# SAMD51_SoundHub_Pro_1_0_0_may2023.net
KiCad netlist of a schematic drawn in EAGLE
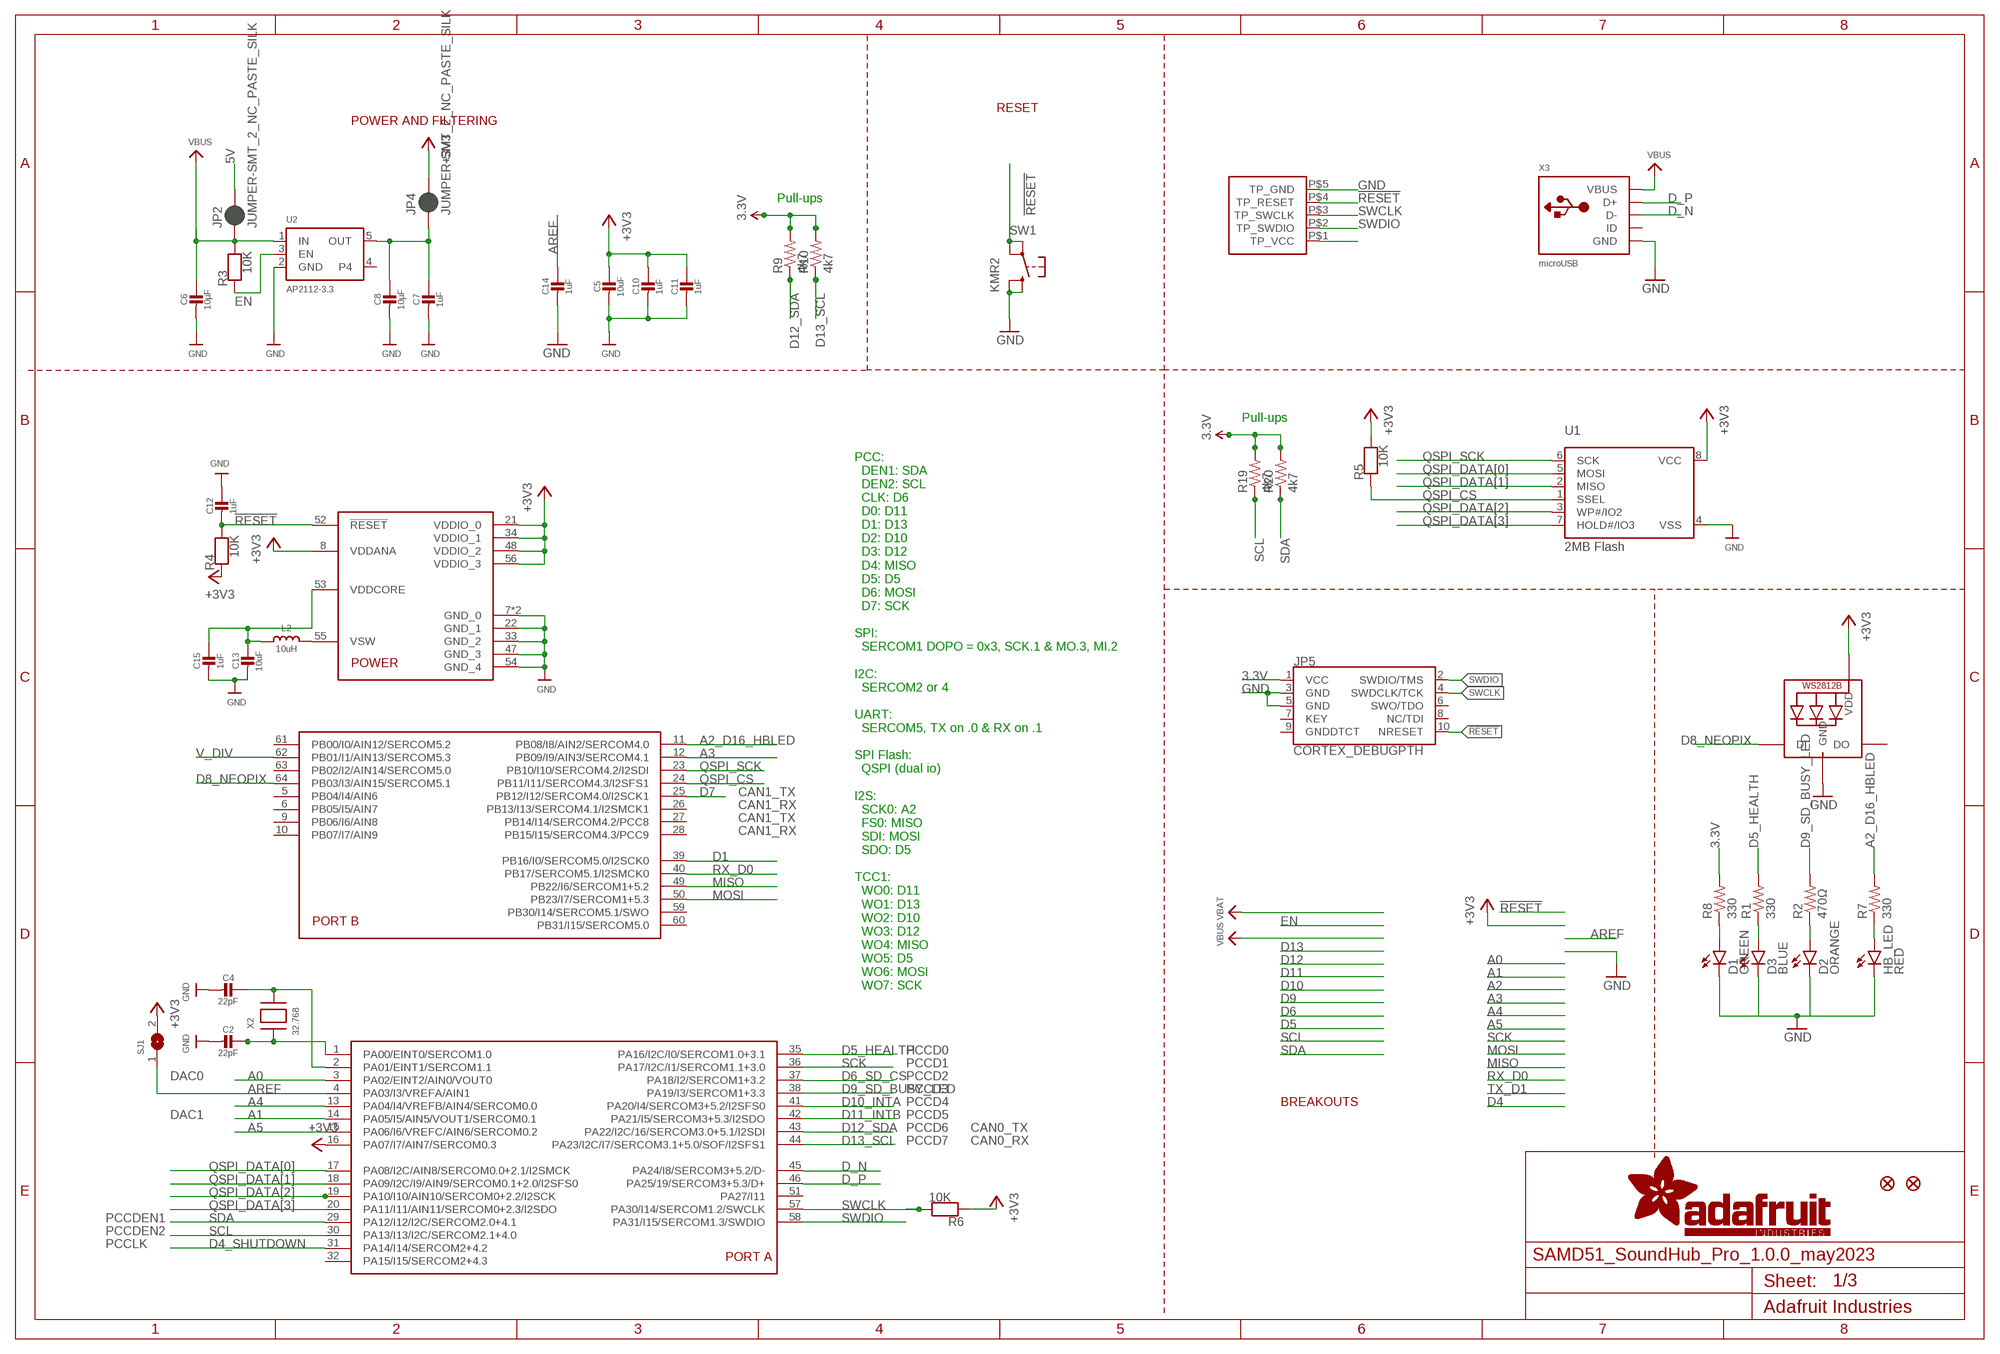
[diagram p0: schematic, sheet 1]
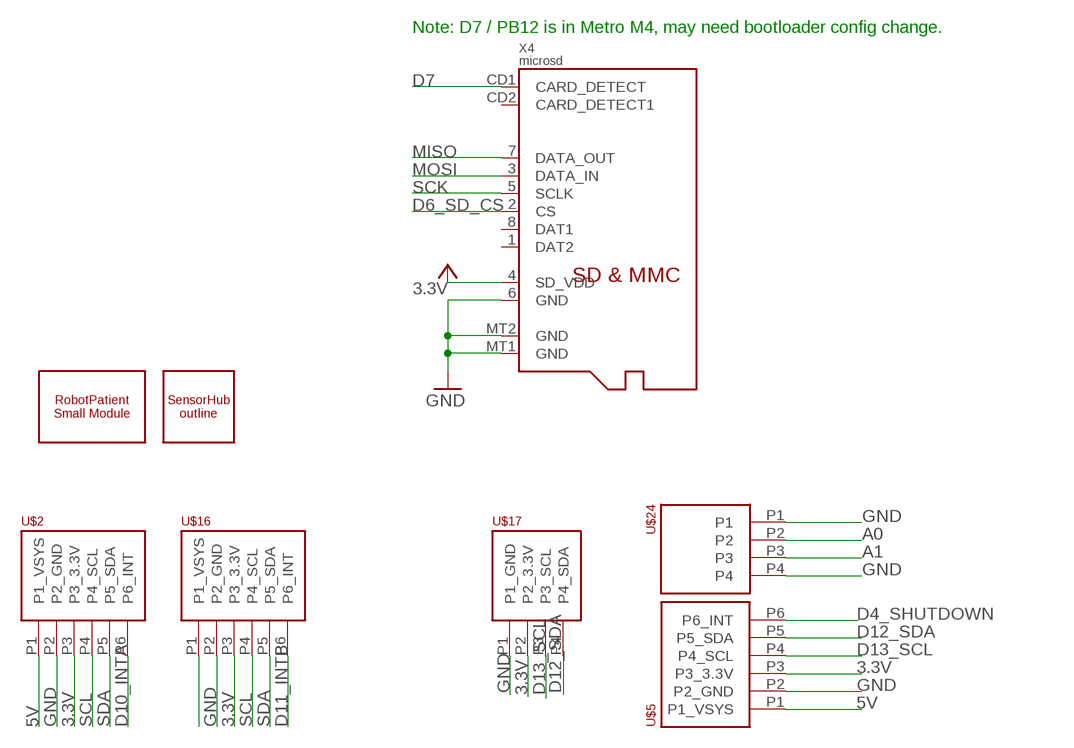
[diagram p1: schematic, sheet 2]

(export (version "E")
  (design (tool "Eeschema 10.0.6"))
  (components
    (comp (ref "C2")
      (value "22pF")
      (footprint "eagle-import:0603-NO")
      (libsource (lib "eagle-import") (part "CAP_CERAMIC0603_NO"))
    )
    (comp (ref "C4")
      (value "22pF")
      (footprint "eagle-import:0603-NO")
      (libsource (lib "eagle-import") (part "CAP_CERAMIC0603_NO"))
    )
    (comp (ref "C5")
      (value "10uF")
      (footprint "eagle-import:0805-NO")
      (libsource (lib "eagle-import") (part "CAP_CERAMIC0805-NOOUTLINE"))
    )
    (comp (ref "C6")
      (value "10µF")
      (footprint "eagle-import:0805-NO")
      (libsource (lib "eagle-import") (part "CAP_CERAMIC0805-NOOUTLINE"))
    )
    (comp (ref "C7")
      (value "1uF")
      (footprint "eagle-import:0603-NO")
      (libsource (lib "eagle-import") (part "CAP_CERAMIC0603_NO"))
    )
    (comp (ref "C8")
      (value "10µF")
      (footprint "eagle-import:0805-NO")
      (fields (field (name "REV") "E"))
      (libsource (lib "eagle-import") (part "CAP_CERAMIC0805-NOOUTLINE"))
    )
    (comp (ref "C10")
      (value "1uF")
      (footprint "eagle-import:0603-NO")
      (libsource (lib "eagle-import") (part "CAP_CERAMIC0603_NO"))
    )
    (comp (ref "C11")
      (value "1uF")
      (footprint "eagle-import:0603-NO")
      (libsource (lib "eagle-import") (part "CAP_CERAMIC0603_NO"))
    )
    (comp (ref "C12")
      (value "1uF")
      (footprint "eagle-import:0603-NO")
      (libsource (lib "eagle-import") (part "CAP_CERAMIC0603_NO"))
    )
    (comp (ref "C13")
      (value "10uF")
      (footprint "eagle-import:0805-NO")
      (libsource (lib "eagle-import") (part "CAP_CERAMIC0805-NOOUTLINE"))
    )
    (comp (ref "C14")
      (value "1uF")
      (footprint "eagle-import:0603-NO")
      (libsource (lib "eagle-import") (part "CAP_CERAMIC0603_NO"))
    )
    (comp (ref "C15")
      (value "1uF")
      (footprint "eagle-import:0603-NO")
      (libsource (lib "eagle-import") (part "CAP_CERAMIC0603_NO"))
    )
    (comp (ref "D1")
      (value "GREEN")
      (footprint "eagle-import:LED-0603@1")
      (libsource (lib "eagle-import") (part "LED-BLUE0603"))
    )
    (comp (ref "D2")
      (value "ORANGE")
      (footprint "eagle-import:LED-0603")
      (libsource (lib "eagle-import") (part "LED-RED0603"))
    )
    (comp (ref "D3")
      (value "BLUE")
      (footprint "eagle-import:LED-0603@1")
      (libsource (lib "eagle-import") (part "LED-BLUE0603"))
    )
    (comp (ref "HB_LED")
      (value "RED")
      (footprint "eagle-import:LED-0603")
      (libsource (lib "eagle-import") (part "LED-RED0603"))
    )
    (comp (ref "JP2")
      (value "JUMPER-SMT_2_NC_PASTE_SILK")
      (footprint "eagle-import:SMT-JUMPER_2_NC_PASTE_SILK")
      (libsource (lib "eagle-import") (part "JUMPER-SMT_2_NC_PASTE_SILK"))
    )
    (comp (ref "JP4")
      (value "JUMPER-SMT_2_NC_PASTE_SILK")
      (footprint "eagle-import:SMT-JUMPER_2_NC_PASTE_SILK")
      (libsource (lib "eagle-import") (part "JUMPER-SMT_2_NC_PASTE_SILK"))
    )
    (comp (ref "JP5")
      (value "CORTEX_DEBUGPTH")
      (footprint "eagle-import:2X5-PTH-1.27MM")
      (libsource (lib "eagle-import") (part "CORTEX_DEBUGPTH"))
    )
    (comp (ref "L2")
      (value "10uH")
      (footprint "eagle-import:INDUCTOR_1007")
      (libsource (lib "eagle-import") (part "INDUCTOR"))
    )
    (comp (ref "LED1")
      (value "WS2812B3535")
      (footprint "eagle-import:LED3535")
      (libsource (lib "eagle-import") (part "WS2812B3535"))
    )
    (comp (ref "R1")
      (value "330")
      (footprint "eagle-import:0603-RES")
      (libsource (lib "eagle-import") (part "330OHM1/10W1%(0603)"))
    )
    (comp (ref "R2")
      (value "470Ω")
      (footprint "eagle-import:0603-RES")
      (libsource (lib "eagle-import") (part "330OHM1/10W1%(0603)"))
    )
    (comp (ref "R3")
      (value "10K")
      (footprint "eagle-import:0603-NO")
      (libsource (lib "eagle-import") (part "RESISTOR_0603_NOOUT"))
    )
    (comp (ref "R4")
      (value "10K")
      (footprint "eagle-import:0603-NO")
      (libsource (lib "eagle-import") (part "RESISTOR_0603_NOOUT"))
    )
    (comp (ref "R5")
      (value "10K")
      (footprint "eagle-import:0603-NO")
      (libsource (lib "eagle-import") (part "RESISTOR_0603_NOOUT"))
    )
    (comp (ref "R6")
      (value "10K")
      (footprint "eagle-import:0603-NO")
      (libsource (lib "eagle-import") (part "RESISTOR_0603_NOOUT"))
    )
    (comp (ref "R7")
      (value "330")
      (footprint "eagle-import:0603-RES")
      (libsource (lib "eagle-import") (part "330OHM1/10W1%(0603)"))
    )
    (comp (ref "R8")
      (value "330")
      (footprint "eagle-import:0603-RES")
      (libsource (lib "eagle-import") (part "330OHM1/10W1%(0603)"))
    )
    (comp (ref "R9")
      (value "4k7")
      (footprint "eagle-import:0603-RES")
      (libsource (lib "eagle-import") (part "47KOHM1/10W1%(0603)"))
    )
    (comp (ref "R10")
      (value "4k7")
      (footprint "eagle-import:0603-RES")
      (libsource (lib "eagle-import") (part "47KOHM1/10W1%(0603)"))
    )
    (comp (ref "R19")
      (value "4k7")
      (footprint "eagle-import:0603-RES")
      (libsource (lib "eagle-import") (part "47KOHM1/10W1%(0603)"))
    )
    (comp (ref "R20")
      (value "4k7")
      (footprint "eagle-import:0603-RES")
      (libsource (lib "eagle-import") (part "47KOHM1/10W1%(0603)"))
    )
    (comp (ref "SJ1")
      (value "SOLDERJUMPERCLOSED")
      (footprint "eagle-import:SOLDERJUMPER_CLOSEDWIRE")
      (libsource (lib "eagle-import") (part "SOLDERJUMPERCLOSED"))
    )
    (comp (ref "SW1")
      (value "KMR2")
      (footprint "eagle-import:BTN_KMR2_4.6X2.8")
      (libsource (lib "eagle-import") (part "SWITCH_TACT_SMT4.6X2.8"))
    )
    (comp (ref "U$12")
      (value "HUB_TESTPINSHUBS")
      (footprint "eagle-import:TEST_PINS")
      (libsource (lib "eagle-import") (part "HUB_TESTPINSHUBS"))
    )
    (comp (ref "U$14")
      (value "ATSAMD51J")
      (footprint "eagle-import:PQFN64-1")
      (libsource (lib "eagle-import") (part "ATSAMD51J"))
    )
    (comp (ref "U$34")
      (value "FIDUCIAL_1MM")
      (footprint "eagle-import:FIDUCIAL_1MM")
      (libsource (lib "eagle-import") (part "FIDUCIAL_1MM"))
    )
    (comp (ref "U$35")
      (value "FIDUCIAL_1MM")
      (footprint "eagle-import:FIDUCIAL_1MM")
      (libsource (lib "eagle-import") (part "FIDUCIAL_1MM"))
    )
    (comp (ref "U1")
      (value "2MB Flash")
      (footprint "eagle-import:USON8")
      (libsource (lib "eagle-import") (part "SPIFLASH_8PINUX"))
    )
    (comp (ref "U2")
      (value "AP2112-3.3")
      (footprint "eagle-import:SOT23-5")
      (libsource (lib "eagle-import") (part "VREG_SOT23-5"))
    )
    (comp (ref "X2")
      (value "32.768")
      (footprint "eagle-import:XTAL3215")
      (libsource (lib "eagle-import") (part "XTAL-3.2X1.5"))
    )
    (comp (ref "X3")
      (value "microUSB")
      (footprint "eagle-import:4UCONN_20329_V2")
      (libsource (lib "eagle-import") (part "USB_MICRO_20329_V2"))
    )
    (comp (ref "U$2")
      (value "PHOENIX_PTSM_M6_TH_I2CPPANGLE")
      (footprint "eagle-import:PTSM_M6_THRHOLE")
      (libsource (lib "eagle-import") (part "PHOENIX_PTSM_M6_TH_I2CPPANGLE"))
    )
    (comp (ref "U$5")
      (value "PHOENIX_PTSM_M6_TH_I2CPPANGLE")
      (footprint "eagle-import:PTSM_M6_THRHOLE")
      (libsource (lib "eagle-import") (part "PHOENIX_PTSM_M6_TH_I2CPPANGLE"))
    )
    (comp (ref "U$7")
      (value "SENSORHUB_PROFILEUSB_LEFT")
      (footprint "eagle-import:SENSORHUB_OUTLINE_USB_NOTCH_LEFT")
      (libsource (lib "eagle-import") (part "SENSORHUB_PROFILEUSB_LEFT"))
    )
    (comp (ref "U$9")
      (value "ROBOTPATIENT_SMALL_MODULEOUTLINE")
      (footprint "eagle-import:ROBOTPATIENT_SMALL")
      (libsource (lib "eagle-import") (part "ROBOTPATIENT_SMALL_MODULEOUTLINE"))
    )
    (comp (ref "U$16")
      (value "PHOENIX_PTSM_M6_TH_I2CPPANGLE")
      (footprint "eagle-import:PTSM_M6_THRHOLE")
      (libsource (lib "eagle-import") (part "PHOENIX_PTSM_M6_TH_I2CPPANGLE"))
    )
    (comp (ref "U$17")
      (value "PHOENIX_PTSM_M4_THANGLE")
      (footprint "eagle-import:PTSM_M4_TH")
      (libsource (lib "eagle-import") (part "PHOENIX_PTSM_M4_THANGLE"))
    )
    (comp (ref "U$24")
      (value "PHOENIX_PTSM_M4_TH_ANGLE")
      (footprint "eagle-import:PTSM_M4_TH_ANGLE_NEUTRAL")
      (libsource (lib "eagle-import") (part "PHOENIX_PTSM_M4_TH_ANGLE"))
    )
    (comp (ref "X4")
      (value "microsd")
      (footprint "eagle-import:MICROSD")
      (libsource (lib "eagle-import") (part "MICROSD"))
    )
  )
  (nets
    (net (code "1") (name "3.3V") (class "Default")
      (node (ref "C10") (pin "1") (pinfunction "1_1") (pintype "passive"))
      (node (ref "C11") (pin "1") (pinfunction "1_1") (pintype "passive"))
      (node (ref "C5") (pin "1") (pinfunction "1_1") (pintype "passive"))
      (node (ref "JP4") (pin "2") (pinfunction "2_2") (pintype "passive"))
      (node (ref "JP5") (pin "1") (pinfunction "VCC_1") (pintype "bidirectional"))
      (node (ref "LED1") (pin "2") (pinfunction "VDD_2") (pintype "power_in"))
      (node (ref "R10") (pin "2") (pinfunction "2_2") (pintype "passive"))
      (node (ref "R19") (pin "2") (pinfunction "2_2") (pintype "passive"))
      (node (ref "R20") (pin "2") (pinfunction "2_2") (pintype "passive"))
      (node (ref "R4") (pin "1") (pinfunction "1_1") (pintype "passive"))
      (node (ref "R5") (pin "2") (pinfunction "2_2") (pintype "passive"))
      (node (ref "R6") (pin "1") (pinfunction "1_1") (pintype "passive"))
      (node (ref "R8") (pin "2") (pinfunction "2_2") (pintype "passive"))
      (node (ref "R9") (pin "2") (pinfunction "2_2") (pintype "passive"))
      (node (ref "SJ1") (pin "2") (pinfunction "2_2") (pintype "passive"))
      (node (ref "U$12") (pin "P$1") (pinfunction "TP_VCC_P$1") (pintype "bidirectional"))
      (node (ref "U$14") (pin "16") (pinfunction "PA07/I7/AIN7/SERCOM0.3_16") (pintype "bidirectional"))
      (node (ref "U$14") (pin "21") (pinfunction "VDDIO_0_21") (pintype "bidirectional"))
      (node (ref "U$14") (pin "34") (pinfunction "VDDIO_1_34") (pintype "bidirectional"))
      (node (ref "U$14") (pin "48") (pinfunction "VDDIO_2_48") (pintype "bidirectional"))
      (node (ref "U$14") (pin "56") (pinfunction "VDDIO_3_56") (pintype "bidirectional"))
      (node (ref "U$14") (pin "8") (pinfunction "VDDANA_8") (pintype "bidirectional"))
      (node (ref "U$16") (pin "P3") (pinfunction "P3_3.3V_P3") (pintype "power_in"))
      (node (ref "U$17") (pin "P2") (pinfunction "P2_3.3V_P2") (pintype "power_in"))
      (node (ref "U$2") (pin "P3") (pinfunction "P3_3.3V_P3") (pintype "power_in"))
      (node (ref "U$5") (pin "P3") (pinfunction "P3_3.3V_P3") (pintype "power_in"))
      (node (ref "U1") (pin "8") (pinfunction "VCC_8") (pintype "bidirectional"))
      (node (ref "X4") (pin "4") (pinfunction "SD_VDD_4") (pintype "power_in"))
    )
    (net (code "2") (name "5V") (class "Default")
      (node (ref "JP2") (pin "2") (pinfunction "2_2") (pintype "passive"))
      (node (ref "U$16") (pin "P1") (pinfunction "P1_VSYS_P1") (pintype "power_in"))
      (node (ref "U$2") (pin "P1") (pinfunction "P1_VSYS_P1") (pintype "power_in"))
      (node (ref "U$5") (pin "P1") (pinfunction "P1_VSYS_P1") (pintype "power_in"))
    )
    (net (code "3") (name "A0") (class "Default")
      (node (ref "U$14") (pin "3") (pinfunction "PA02/EINT2/AIN0/VOUT0_3") (pintype "bidirectional"))
      (node (ref "U$24") (pin "P2") (pinfunction "P2_P2") (pintype "power_in"))
    )
    (net (code "4") (name "A1") (class "Default")
      (node (ref "U$14") (pin "14") (pinfunction "PA05/I5/AIN5/VOUT1/SERCOM0.1_14") (pintype "bidirectional"))
      (node (ref "U$24") (pin "P3") (pinfunction "P3_P3") (pintype "power_in"))
    )
    (net (code "6") (name "A2_D16_HBLED") (class "Default")
      (node (ref "R7") (pin "2") (pinfunction "2_2") (pintype "passive"))
      (node (ref "U$14") (pin "11") (pinfunction "PB08/I8/AIN2/SERCOM4.0_11") (pintype "bidirectional"))
    )
    (net (code "7") (name "A3") (class "Default")
      (node (ref "U$14") (pin "12") (pinfunction "PB09/I9/AIN3/SERCOM4.1_12") (pintype "bidirectional"))
    )
    (net (code "8") (name "A4") (class "Default")
      (node (ref "U$14") (pin "13") (pinfunction "PA04/I4/VREFB/AIN4/SERCOM0.0_13") (pintype "bidirectional"))
    )
    (net (code "9") (name "A5") (class "Default")
      (node (ref "U$14") (pin "15") (pinfunction "PA06/I6/VREFC/AIN6/SERCOM0.2_15") (pintype "bidirectional"))
    )
    (net (code "10") (name "AREF") (class "Default")
      (node (ref "C14") (pin "1") (pinfunction "1_1") (pintype "passive"))
      (node (ref "SJ1") (pin "1") (pinfunction "1_1") (pintype "passive"))
      (node (ref "U$14") (pin "4") (pinfunction "PA03/I3/VREFA/AIN1_4") (pintype "bidirectional"))
    )
    (net (code "11") (name "D1") (class "Default")
      (node (ref "U$14") (pin "39") (pinfunction "PB16/I0/SERCOM5.0/I2SCK0_39") (pintype "bidirectional"))
    )
    (net (code "13") (name "D4_SHUTDOWN") (class "Default")
      (node (ref "U$14") (pin "31") (pinfunction "PA14/I14/SERCOM2+4.2_31") (pintype "bidirectional"))
      (node (ref "U$5") (pin "P6") (pinfunction "P6_INT_P6") (pintype "power_in"))
    )
    (net (code "15") (name "D5_HEALTH") (class "Default")
      (node (ref "R1") (pin "2") (pinfunction "2_2") (pintype "passive"))
      (node (ref "U$14") (pin "35") (pinfunction "PA16/I2C/I0/SERCOM1.0+3.1_35") (pintype "bidirectional"))
    )
    (net (code "17") (name "D6_SD_CS") (class "Default")
      (node (ref "U$14") (pin "37") (pinfunction "PA18/I2/SERCOM1+3.2_37") (pintype "bidirectional"))
      (node (ref "X4") (pin "2") (pinfunction "CS_2") (pintype "input"))
    )
    (net (code "18") (name "D7") (class "Default")
      (node (ref "U$14") (pin "25") (pinfunction "PB12/I12/SERCOM4.0/I2SCK1_25") (pintype "bidirectional"))
      (node (ref "X4") (pin "CD1") (pinfunction "CARD_DETECT_CD1") (pintype "passive"))
    )
    (net (code "19") (name "D8_NEOPIX") (class "Default")
      (node (ref "LED1") (pin "1") (pinfunction "DI_1") (pintype "input"))
      (node (ref "U$14") (pin "64") (pinfunction "PB03/I3/AIN15/SERCOM5.1_64") (pintype "bidirectional"))
    )
    (net (code "21") (name "D9_SD_BUSY_LED") (class "Default")
      (node (ref "R2") (pin "2") (pinfunction "2_2") (pintype "passive"))
      (node (ref "U$14") (pin "38") (pinfunction "PA19/I3/SERCOM1+3.3_38") (pintype "bidirectional"))
    )
    (net (code "23") (name "D10_INTA") (class "Default")
      (node (ref "U$14") (pin "41") (pinfunction "PA20/I4/SERCOM3+5.2/I2SFS0_41") (pintype "bidirectional"))
      (node (ref "U$2") (pin "P6") (pinfunction "P6_INT_P6") (pintype "power_in"))
    )
    (net (code "25") (name "D11_INTB") (class "Default")
      (node (ref "U$14") (pin "42") (pinfunction "PA21/I5/SERCOM3+5.3/I2SDO_42") (pintype "bidirectional"))
      (node (ref "U$16") (pin "P6") (pinfunction "P6_INT_P6") (pintype "power_in"))
    )
    (net (code "27") (name "D12_SDA") (class "Default")
      (node (ref "R9") (pin "1") (pinfunction "1_1") (pintype "passive"))
      (node (ref "U$14") (pin "43") (pinfunction "PA22/I2C/16/SERCOM3.0+5.1/I2SDI_43") (pintype "bidirectional"))
      (node (ref "U$17") (pin "P4") (pinfunction "P4_SDA_P4") (pintype "bidirectional"))
      (node (ref "U$5") (pin "P5") (pinfunction "P5_SDA_P5") (pintype "bidirectional"))
    )
    (net (code "29") (name "D13_SCL") (class "Default")
      (node (ref "R10") (pin "1") (pinfunction "1_1") (pintype "passive"))
      (node (ref "U$14") (pin "44") (pinfunction "PA23/I2C/I7/SERCOM3.1+5.0/SOF/I2SFS1_44") (pintype "bidirectional"))
      (node (ref "U$17") (pin "P3") (pinfunction "P3_SCL_P3") (pintype "bidirectional"))
      (node (ref "U$5") (pin "P4") (pinfunction "P4_SCL_P4") (pintype "bidirectional"))
    )
    (net (code "30") (name "D_N") (class "Default")
      (node (ref "U$14") (pin "45") (pinfunction "PA24/I8/SERCOM3+5.2/D-_45") (pintype "bidirectional"))
      (node (ref "X3") (pin "D-") (pinfunction "D-_D-") (pintype "bidirectional"))
    )
    (net (code "31") (name "D_P") (class "Default")
      (node (ref "U$14") (pin "46") (pinfunction "PA25/19/SERCOM3+5.3/D+_46") (pintype "bidirectional"))
      (node (ref "X3") (pin "D+") (pinfunction "D+_D+") (pintype "bidirectional"))
    )
    (net (code "32") (name "EN") (class "Default")
      (node (ref "R3") (pin "1") (pinfunction "1_1") (pintype "passive"))
      (node (ref "U2") (pin "3") (pinfunction "EN_3") (pintype "input"))
    )
    (net (code "33") (name "GND") (class "Default")
      (node (ref "C10") (pin "2") (pinfunction "2_2") (pintype "passive"))
      (node (ref "C11") (pin "2") (pinfunction "2_2") (pintype "passive"))
      (node (ref "C12") (pin "1") (pinfunction "1_1") (pintype "passive"))
      (node (ref "C13") (pin "2") (pinfunction "2_2") (pintype "passive"))
      (node (ref "C14") (pin "2") (pinfunction "2_2") (pintype "passive"))
      (node (ref "C15") (pin "2") (pinfunction "2_2") (pintype "passive"))
      (node (ref "C2") (pin "2") (pinfunction "2_2") (pintype "passive"))
      (node (ref "C4") (pin "2") (pinfunction "2_2") (pintype "passive"))
      (node (ref "C5") (pin "2") (pinfunction "2_2") (pintype "passive"))
      (node (ref "C6") (pin "2") (pinfunction "2_2") (pintype "passive"))
      (node (ref "C7") (pin "2") (pinfunction "2_2") (pintype "passive"))
      (node (ref "C8") (pin "2") (pinfunction "2_2") (pintype "passive"))
      (node (ref "D1") (pin "C") (pinfunction "C_C") (pintype "passive"))
      (node (ref "HB_LED") (pin "C") (pinfunction "C_C") (pintype "passive"))
      (node (ref "JP5") (pin "3") (pinfunction "GND_3") (pintype "bidirectional"))
      (node (ref "JP5") (pin "5") (pinfunction "GND_5") (pintype "bidirectional"))
      (node (ref "LED1") (pin "4") (pinfunction "GND_4") (pintype "power_in"))
      (node (ref "SW1") (pin "B") (pinfunction "S_B") (pintype "passive"))
      (node (ref "SW1") (pin "B'") (pinfunction "S1_B'") (pintype "passive"))
      (node (ref "U$12") (pin "P$5") (pinfunction "TP_GND_P$5") (pintype "bidirectional"))
      (node (ref "U$14") (pin "22") (pinfunction "GND_1_22") (pintype "bidirectional"))
      (node (ref "U$14") (pin "33") (pinfunction "GND_2_33") (pintype "bidirectional"))
      (node (ref "U$14") (pin "47") (pinfunction "GND_3_47") (pintype "bidirectional"))
      (node (ref "U$14") (pin "54") (pinfunction "GND_4_54") (pintype "bidirectional"))
      (node (ref "U$14") (pin "7") (pinfunction "GND_0_7") (pintype "bidirectional"))
      (node (ref "U$14") (pin "EXP") (pinfunction "GND_0_EXP") (pintype "bidirectional"))
      (node (ref "U$16") (pin "P2") (pinfunction "P2_GND_P2") (pintype "power_in"))
      (node (ref "U$17") (pin "P1") (pinfunction "P1_GND_P1") (pintype "power_in"))
      (node (ref "U$2") (pin "P2") (pinfunction "P2_GND_P2") (pintype "power_in"))
      (node (ref "U$24") (pin "P1") (pinfunction "P1_P1") (pintype "power_in"))
      (node (ref "U$24") (pin "P4") (pinfunction "P4_P4") (pintype "power_in"))
      (node (ref "U$5") (pin "P2") (pinfunction "P2_GND_P2") (pintype "power_in"))
      (node (ref "U1") (pin "4") (pinfunction "VSS_4") (pintype "bidirectional"))
      (node (ref "U2") (pin "2") (pinfunction "GND_2") (pintype "power_in"))
      (node (ref "X3") (pin "BASE@1") (pinfunction "GND_BASE@1") (pintype "power_in"))
      (node (ref "X3") (pin "BASE@2") (pinfunction "GND_BASE@2") (pintype "power_in"))
      (node (ref "X3") (pin "GND") (pinfunction "GND_GND") (pintype "power_in"))
      (node (ref "X3") (pin "SPRT@1") (pinfunction "GND_SPRT@1") (pintype "power_in"))
      (node (ref "X3") (pin "SPRT@2") (pinfunction "GND_SPRT@2") (pintype "power_in"))
      (node (ref "X3") (pin "SPRT@3") (pinfunction "GND_SPRT@3") (pintype "power_in"))
      (node (ref "X3") (pin "SPRT@4") (pinfunction "GND_SPRT@4") (pintype "power_in"))
      (node (ref "X4") (pin "6") (pinfunction "GND_6") (pintype "power_in"))
      (node (ref "X4") (pin "MT1") (pinfunction "GND_MT1") (pintype "power_in"))
      (node (ref "X4") (pin "MT2") (pinfunction "GND_MT2") (pintype "power_in"))
    )
    (net (code "34") (name "MISO") (class "Default")
      (node (ref "U$14") (pin "49") (pinfunction "PB22/I6/SERCOM1+5.2_49") (pintype "bidirectional"))
      (node (ref "X4") (pin "7") (pinfunction "DATA_OUT_7") (pintype "output"))
    )
    (net (code "35") (name "MOSI") (class "Default")
      (node (ref "U$14") (pin "50") (pinfunction "PB23/I7/SERCOM1+5.3_50") (pintype "bidirectional"))
      (node (ref "X4") (pin "3") (pinfunction "DATA_IN_3") (pintype "input"))
    )
    (net (code "36") (name "Net-(D1-PadA)") (class "Default")
      (node (ref "D1") (pin "A") (pinfunction "A_A") (pintype "passive"))
      (node (ref "R8") (pin "1") (pinfunction "1_1") (pintype "passive"))
    )
    (net (code "37") (name "Net-(D2-PadA)") (class "Default")
      (node (ref "D2") (pin "A") (pinfunction "A_A") (pintype "passive"))
      (node (ref "R2") (pin "1") (pinfunction "1_1") (pintype "passive"))
    )
    (net (code "38") (name "Net-(D3-PadA)") (class "Default")
      (node (ref "D3") (pin "A") (pinfunction "A_A") (pintype "passive"))
      (node (ref "R1") (pin "1") (pinfunction "1_1") (pintype "passive"))
    )
    (net (code "39") (name "Net-(HB_LED-PadA)") (class "Default")
      (node (ref "HB_LED") (pin "A") (pinfunction "A_A") (pintype "passive"))
      (node (ref "R7") (pin "1") (pinfunction "1_1") (pintype "passive"))
    )
    (net (code "40") (name "Net-(L2-1)") (class "Default")
      (node (ref "C13") (pin "1") (pinfunction "1_1") (pintype "passive"))
      (node (ref "C15") (pin "1") (pinfunction "1_1") (pintype "passive"))
      (node (ref "L2") (pin "P$1") (pinfunction "1_P$1") (pintype "passive"))
      (node (ref "U$14") (pin "53") (pinfunction "VDDCORE_53") (pintype "bidirectional"))
    )
    (net (code "41") (name "Net-(L2-2)") (class "Default")
      (node (ref "L2") (pin "P$2") (pinfunction "2_P$2") (pintype "passive"))
      (node (ref "U$14") (pin "55") (pinfunction "VSW_55") (pintype "bidirectional"))
    )
    (net (code "42") (name "Net-(U$14A-PA00{slash}EINT0{slash}SERCOM1.0)") (class "Default")
      (node (ref "C2") (pin "1") (pinfunction "1_1") (pintype "passive"))
      (node (ref "U$14") (pin "1") (pinfunction "PA00/EINT0/SERCOM1.0_1") (pintype "bidirectional"))
      (node (ref "X2") (pin "P$1") (pinfunction "P$1_P$1") (pintype "bidirectional"))
    )
    (net (code "43") (name "Net-(U$14A-PA01{slash}EINT1{slash}SERCOM1.1)") (class "Default")
      (node (ref "C4") (pin "1") (pinfunction "1_1") (pintype "passive"))
      (node (ref "U$14") (pin "2") (pinfunction "PA01/EINT1/SERCOM1.1_2") (pintype "bidirectional"))
      (node (ref "X2") (pin "P$2") (pinfunction "P$2_P$2") (pintype "bidirectional"))
    )
    (net (code "44") (name "Net-(U2-OUT)") (class "Default")
      (node (ref "C7") (pin "1") (pinfunction "1_1") (pintype "passive"))
      (node (ref "C8") (pin "1") (pinfunction "1_1") (pintype "passive"))
      (node (ref "JP4") (pin "1") (pinfunction "1_1") (pintype "passive"))
      (node (ref "U2") (pin "5") (pinfunction "OUT_5") (pintype "power_in"))
    )
    (net (code "45") (name "QSPI_CS") (class "Default")
      (node (ref "R5") (pin "1") (pinfunction "1_1") (pintype "passive"))
      (node (ref "U$14") (pin "24") (pinfunction "PB11/I11/SERCOM4.3/I2SFS1_24") (pintype "bidirectional"))
      (node (ref "U1") (pin "1") (pinfunction "SSEL_1") (pintype "bidirectional"))
    )
    (net (code "46") (name "QSPI_DATA[0]") (class "Default")
      (node (ref "U$14") (pin "17") (pinfunction "PA08/I2C/AIN8/SERCOM0.0+2.1/I2SMCK_17") (pintype "bidirectional"))
      (node (ref "U1") (pin "5") (pinfunction "MOSI_5") (pintype "bidirectional"))
    )
    (net (code "47") (name "QSPI_DATA[1]") (class "Default")
      (node (ref "U$14") (pin "18") (pinfunction "PA09/I2C/I9/AIN9/SERCOM0.1+2.0/I2SFS0_18") (pintype "bidirectional"))
      (node (ref "U1") (pin "2") (pinfunction "MISO_2") (pintype "bidirectional"))
    )
    (net (code "48") (name "QSPI_DATA[2]") (class "Default")
      (node (ref "U$14") (pin "19") (pinfunction "PA10/I10/AIN10/SERCOM0+2.2/I2SCK_19") (pintype "bidirectional"))
      (node (ref "U1") (pin "3") (pinfunction "WP#/IO2_3") (pintype "bidirectional"))
    )
    (net (code "49") (name "QSPI_DATA[3]") (class "Default")
      (node (ref "U$14") (pin "20") (pinfunction "PA11/I11/AIN11/SERCOM0+2.3/I2SDO_20") (pintype "bidirectional"))
      (node (ref "U1") (pin "7") (pinfunction "HOLD#/IO3_7") (pintype "bidirectional"))
    )
    (net (code "50") (name "QSPI_SCK") (class "Default")
      (node (ref "U$14") (pin "23") (pinfunction "PB10/I10/SERCOM4.2/I2SDI_23") (pintype "bidirectional"))
      (node (ref "U1") (pin "6") (pinfunction "SCK_6") (pintype "bidirectional"))
    )
    (net (code "51") (name "RX_D0") (class "Default")
      (node (ref "U$14") (pin "40") (pinfunction "PB17/SERCOM5.1/I2SMCK0_40") (pintype "bidirectional"))
    )
    (net (code "52") (name "SCK") (class "Default")
      (node (ref "U$14") (pin "36") (pinfunction "PA17/I2C/I1/SERCOM1.1+3.0_36") (pintype "bidirectional"))
      (node (ref "X4") (pin "5") (pinfunction "SCLK_5") (pintype "input"))
    )
    (net (code "53") (name "SCL") (class "Default")
      (node (ref "R19") (pin "1") (pinfunction "1_1") (pintype "passive"))
      (node (ref "U$14") (pin "30") (pinfunction "PA13/I13/I2C/SERCOM2.1+4.0_30") (pintype "bidirectional"))
      (node (ref "U$16") (pin "P4") (pinfunction "P4_SCL_P4") (pintype "bidirectional"))
      (node (ref "U$2") (pin "P4") (pinfunction "P4_SCL_P4") (pintype "bidirectional"))
    )
    (net (code "54") (name "SDA") (class "Default")
      (node (ref "R20") (pin "1") (pinfunction "1_1") (pintype "passive"))
      (node (ref "U$14") (pin "29") (pinfunction "PA12/I12/I2C/SERCOM2.0+4.1_29") (pintype "bidirectional"))
      (node (ref "U$16") (pin "P5") (pinfunction "P5_SDA_P5") (pintype "bidirectional"))
      (node (ref "U$2") (pin "P5") (pinfunction "P5_SDA_P5") (pintype "bidirectional"))
    )
    (net (code "55") (name "SWCLK") (class "Default")
      (node (ref "JP5") (pin "4") (pinfunction "SWDCLK/TCK_4") (pintype "bidirectional"))
      (node (ref "R6") (pin "2") (pinfunction "2_2") (pintype "passive"))
      (node (ref "U$12") (pin "P$3") (pinfunction "TP_SWCLK_P$3") (pintype "bidirectional"))
      (node (ref "U$14") (pin "57") (pinfunction "PA30/I14/SERCOM1.2/SWCLK_57") (pintype "bidirectional"))
    )
    (net (code "56") (name "SWDIO") (class "Default")
      (node (ref "JP5") (pin "2") (pinfunction "SWDIO/TMS_2") (pintype "bidirectional"))
      (node (ref "U$12") (pin "P$2") (pinfunction "TP_SWDIO_P$2") (pintype "bidirectional"))
      (node (ref "U$14") (pin "58") (pinfunction "PA31/I15/SERCOM1.3/SWDIO_58") (pintype "bidirectional"))
    )
    (net (code "59") (name "VBUS") (class "Default")
      (node (ref "C6") (pin "1") (pinfunction "1_1") (pintype "passive"))
      (node (ref "JP2") (pin "1") (pinfunction "1_1") (pintype "passive"))
      (node (ref "R3") (pin "2") (pinfunction "2_2") (pintype "passive"))
      (node (ref "U2") (pin "1") (pinfunction "IN_1") (pintype "power_in"))
      (node (ref "X3") (pin "VBUS") (pinfunction "VBUS_VBUS") (pintype "power_in"))
    )
    (net (code "60") (name "V_DIV") (class "Default")
      (node (ref "U$14") (pin "62") (pinfunction "PB01/I1/AIN13/SERCOM5.3_62") (pintype "bidirectional"))
    )
    (net (code "61") (name "unconnected-(D2-PadC)") (class "Default")
      (node (ref "D2") (pin "C") (pinfunction "C_C") (pintype "passive"))
    )
    (net (code "62") (name "unconnected-(D3-PadC)") (class "Default")
      (node (ref "D3") (pin "C") (pinfunction "C_C") (pintype "passive"))
    )
    (net (code "63") (name "unconnected-(JP5-GNDDTCT-Pad9)") (class "Default")
      (node (ref "JP5") (pin "9") (pinfunction "GNDDTCT_9") (pintype "bidirectional"))
    )
    (net (code "64") (name "unconnected-(JP5-KEY-Pad7)") (class "Default")
      (node (ref "JP5") (pin "7") (pinfunction "KEY_7") (pintype "bidirectional"))
    )
    (net (code "65") (name "unconnected-(JP5-NC{slash}TDI-Pad8)") (class "Default")
      (node (ref "JP5") (pin "8") (pinfunction "NC/TDI_8") (pintype "bidirectional"))
    )
    (net (code "66") (name "unconnected-(JP5-SWO{slash}TDO-Pad6)") (class "Default")
      (node (ref "JP5") (pin "6") (pinfunction "SWO/TDO_6") (pintype "bidirectional"))
    )
    (net (code "67") (name "unconnected-(LED1-DO-Pad3)") (class "Default")
      (node (ref "LED1") (pin "3") (pinfunction "DO_3") (pintype "output"))
    )
    (net (code "68") (name "unconnected-(U$14A-PA15{slash}I15{slash}SERCOM2+4.3-Pad32)") (class "Default")
      (node (ref "U$14") (pin "32") (pinfunction "PA15/I15/SERCOM2+4.3_32") (pintype "bidirectional"))
    )
    (net (code "69") (name "unconnected-(U$14A-PA27{slash}I11-Pad51)") (class "Default")
      (node (ref "U$14") (pin "51") (pinfunction "PA27/I11_51") (pintype "bidirectional"))
    )
    (net (code "70") (name "unconnected-(U$14B-PB00{slash}I0{slash}AIN12{slash}SERCOM5.2-Pad61)") (class "Default")
      (node (ref "U$14") (pin "61") (pinfunction "PB00/I0/AIN12/SERCOM5.2_61") (pintype "bidirectional"))
    )
    (net (code "71") (name "unconnected-(U$14B-PB02{slash}I2{slash}AIN14{slash}SERCOM5.0-Pad63)") (class "Default")
      (node (ref "U$14") (pin "63") (pinfunction "PB02/I2/AIN14/SERCOM5.0_63") (pintype "bidirectional"))
    )
    (net (code "72") (name "unconnected-(U$14B-PB04{slash}I4{slash}AIN6-Pad5)") (class "Default")
      (node (ref "U$14") (pin "5") (pinfunction "PB04/I4/AIN6_5") (pintype "bidirectional"))
    )
    (net (code "73") (name "unconnected-(U$14B-PB05{slash}I5{slash}AIN7-Pad6)") (class "Default")
      (node (ref "U$14") (pin "6") (pinfunction "PB05/I5/AIN7_6") (pintype "bidirectional"))
    )
    (net (code "74") (name "unconnected-(U$14B-PB06{slash}I6{slash}AIN8-Pad9)") (class "Default")
      (node (ref "U$14") (pin "9") (pinfunction "PB06/I6/AIN8_9") (pintype "bidirectional"))
    )
    (net (code "75") (name "unconnected-(U$14B-PB07{slash}I7{slash}AIN9-Pad10)") (class "Default")
      (node (ref "U$14") (pin "10") (pinfunction "PB07/I7/AIN9_10") (pintype "bidirectional"))
    )
    (net (code "76") (name "unconnected-(U$14B-PB13{slash}I13{slash}SERCOM4.1{slash}I2SMCK1-Pad26)") (class "Default")
      (node (ref "U$14") (pin "26") (pinfunction "PB13/I13/SERCOM4.1/I2SMCK1_26") (pintype "bidirectional"))
    )
    (net (code "77") (name "unconnected-(U$14B-PB14{slash}I14{slash}SERCOM4.2{slash}PCC8-Pad27)") (class "Default")
      (node (ref "U$14") (pin "27") (pinfunction "PB14/I14/SERCOM4.2/PCC8_27") (pintype "bidirectional"))
    )
    (net (code "78") (name "unconnected-(U$14B-PB15{slash}I15{slash}SERCOM4.3{slash}PCC9-Pad28)") (class "Default")
      (node (ref "U$14") (pin "28") (pinfunction "PB15/I15/SERCOM4.3/PCC9_28") (pintype "bidirectional"))
    )
    (net (code "79") (name "unconnected-(U$14B-PB30{slash}I14{slash}SERCOM5.1{slash}SWO-Pad59)") (class "Default")
      (node (ref "U$14") (pin "59") (pinfunction "PB30/I14/SERCOM5.1/SWO_59") (pintype "bidirectional"))
    )
    (net (code "80") (name "unconnected-(U$14B-PB31{slash}I15{slash}SERCOM5.0-Pad60)") (class "Default")
      (node (ref "U$14") (pin "60") (pinfunction "PB31/I15/SERCOM5.0_60") (pintype "bidirectional"))
    )
    (net (code "81") (name "unconnected-(U2-P4-Pad4)") (class "Default")
      (node (ref "U2") (pin "4") (pinfunction "P4_4") (pintype "bidirectional"))
    )
    (net (code "82") (name "unconnected-(X3-PadID)") (class "Default")
      (node (ref "X3") (pin "ID") (pinfunction "ID_ID") (pintype "bidirectional"))
    )
    (net (code "83") (name "unconnected-(X4-CARD_DETECT1-PadCD2)") (class "Default")
      (node (ref "X4") (pin "CD2") (pinfunction "CARD_DETECT1_CD2") (pintype "passive"))
    )
    (net (code "84") (name "unconnected-(X4-DAT1-Pad8)") (class "Default")
      (node (ref "X4") (pin "8") (pinfunction "DAT1_8") (pintype "bidirectional"))
    )
    (net (code "85") (name "unconnected-(X4-DAT2-Pad1)") (class "Default")
      (node (ref "X4") (pin "1") (pinfunction "DAT2_1") (pintype "bidirectional"))
    )
    (net (code "86") (name "~{RESET}") (class "Default")
      (node (ref "C12") (pin "2") (pinfunction "2_2") (pintype "passive"))
      (node (ref "JP5") (pin "10") (pinfunction "NRESET_10") (pintype "bidirectional"))
      (node (ref "R4") (pin "2") (pinfunction "2_2") (pintype "passive"))
      (node (ref "SW1") (pin "A") (pinfunction "P_A") (pintype "passive"))
      (node (ref "SW1") (pin "A'") (pinfunction "P1_A'") (pintype "passive"))
      (node (ref "U$12") (pin "P$4") (pinfunction "TP_RESET_P$4") (pintype "bidirectional"))
      (node (ref "U$14") (pin "52") (pinfunction "~{RESET}_52") (pintype "bidirectional"))
    )
  )
)
